# SwirlsV1_0.net
KiCad netlist of a schematic drawn in EAGLE
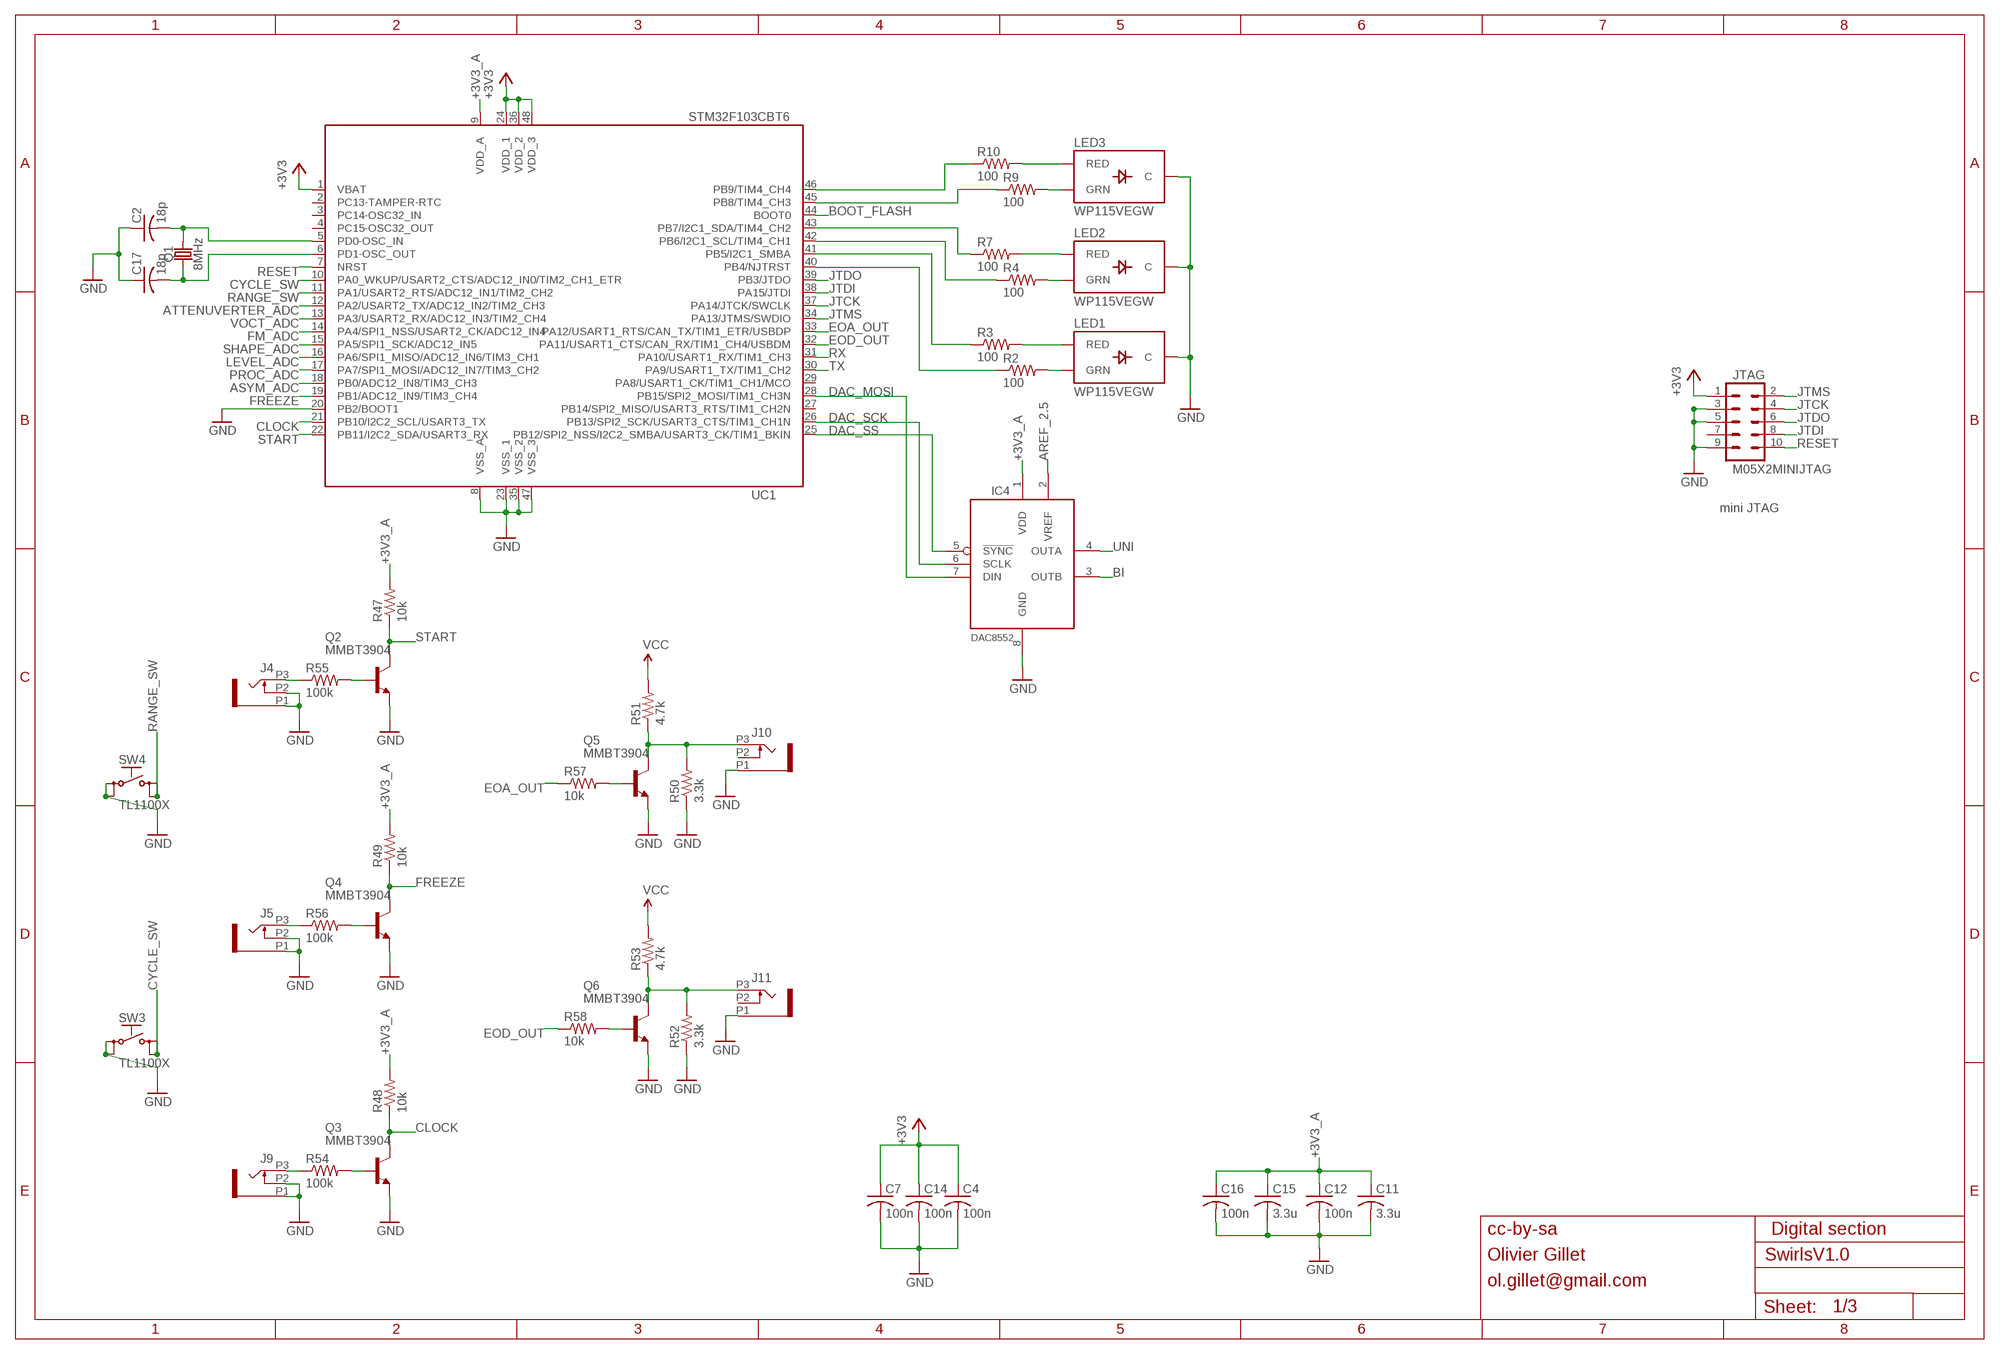
[diagram p0: schematic, sheet 1]
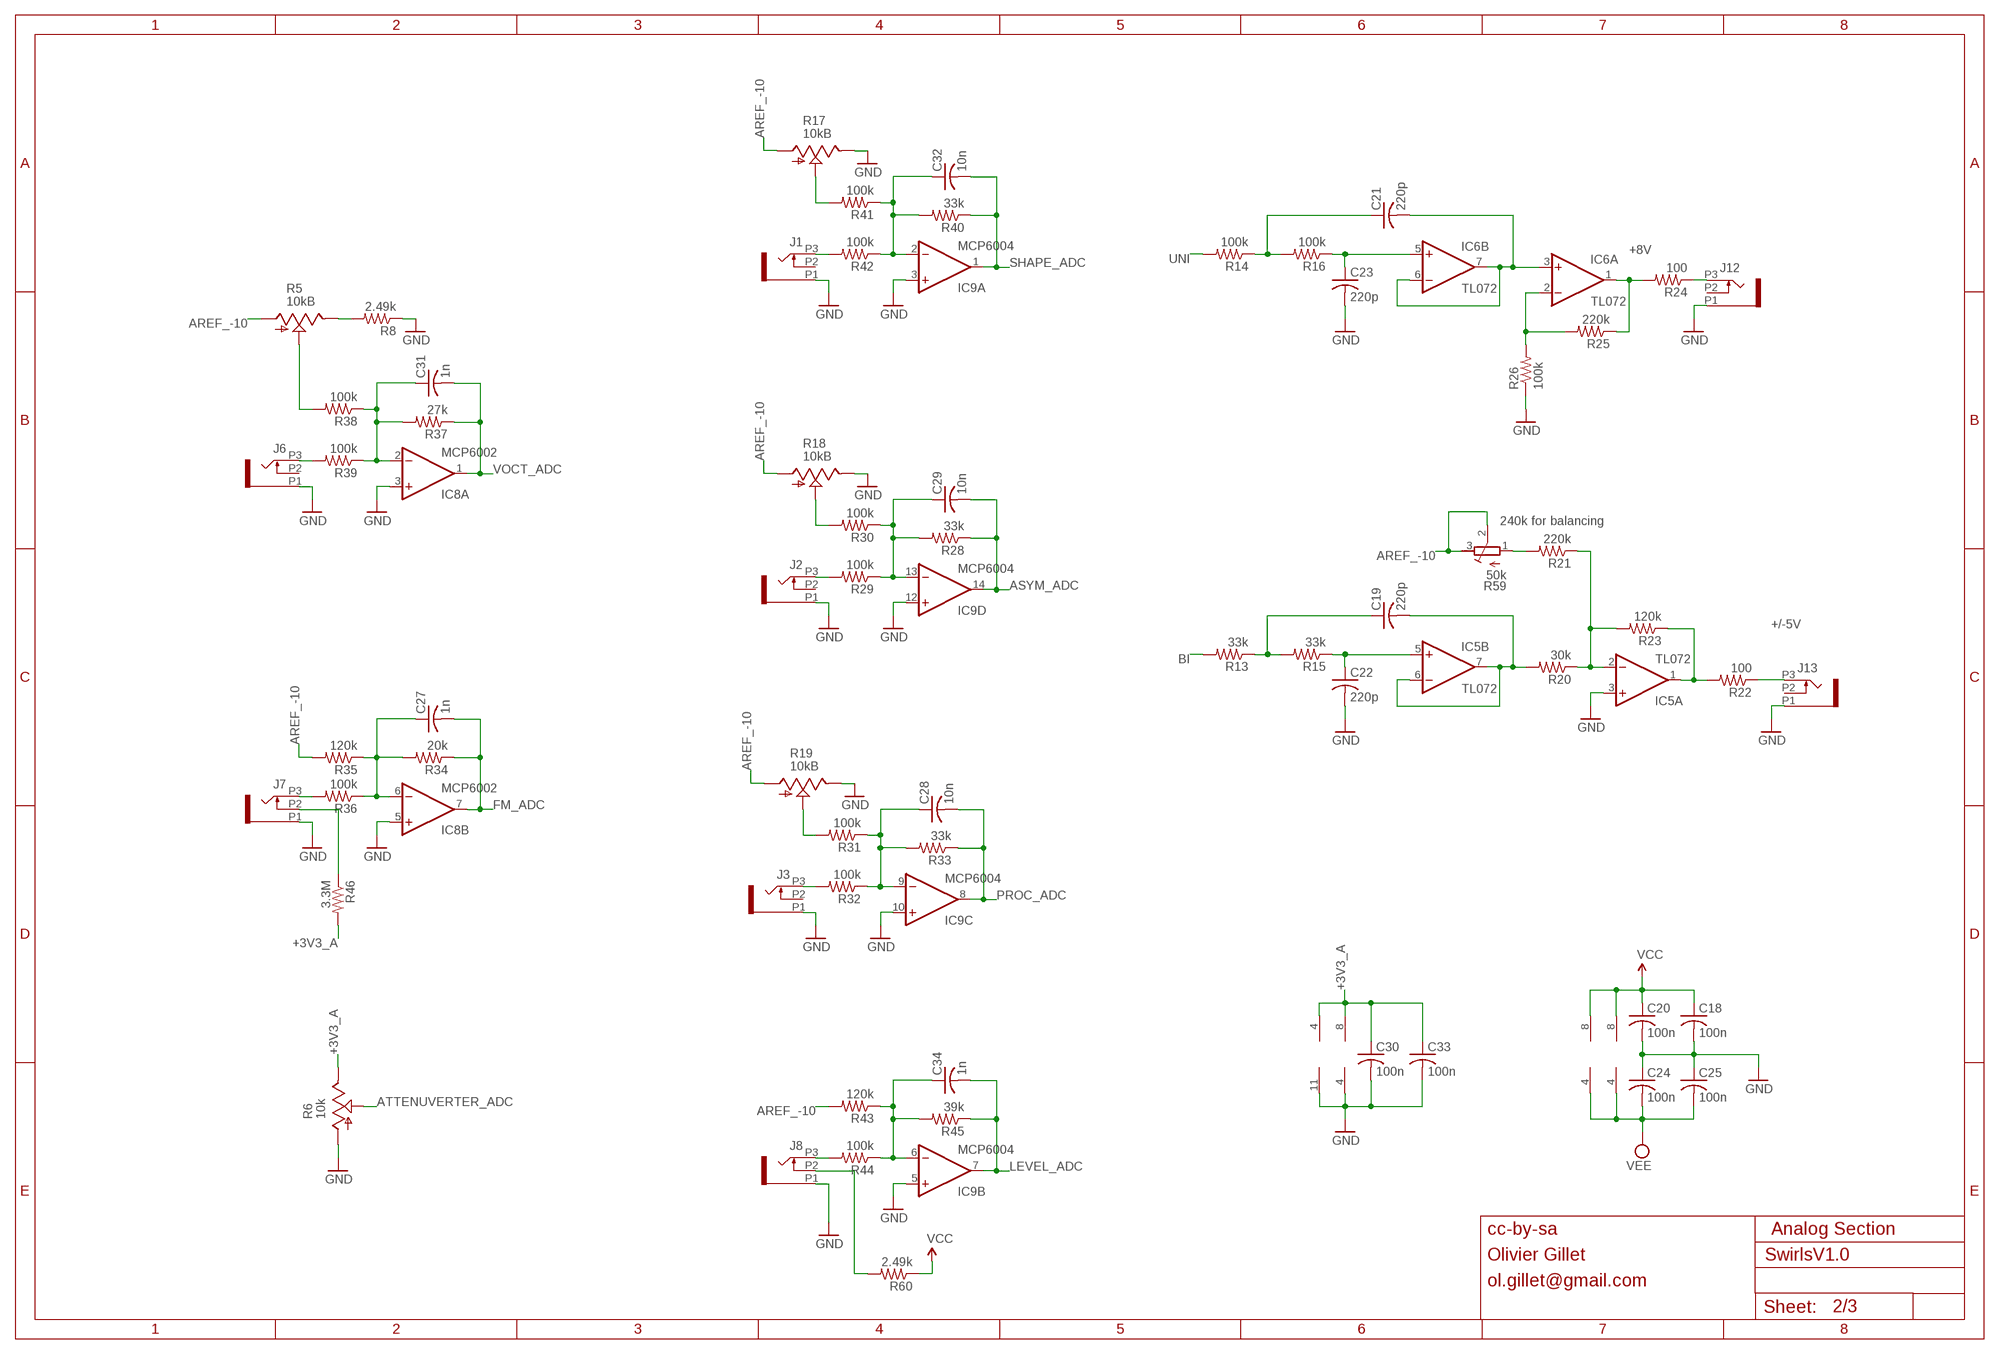
[diagram p1: schematic, sheet 2]
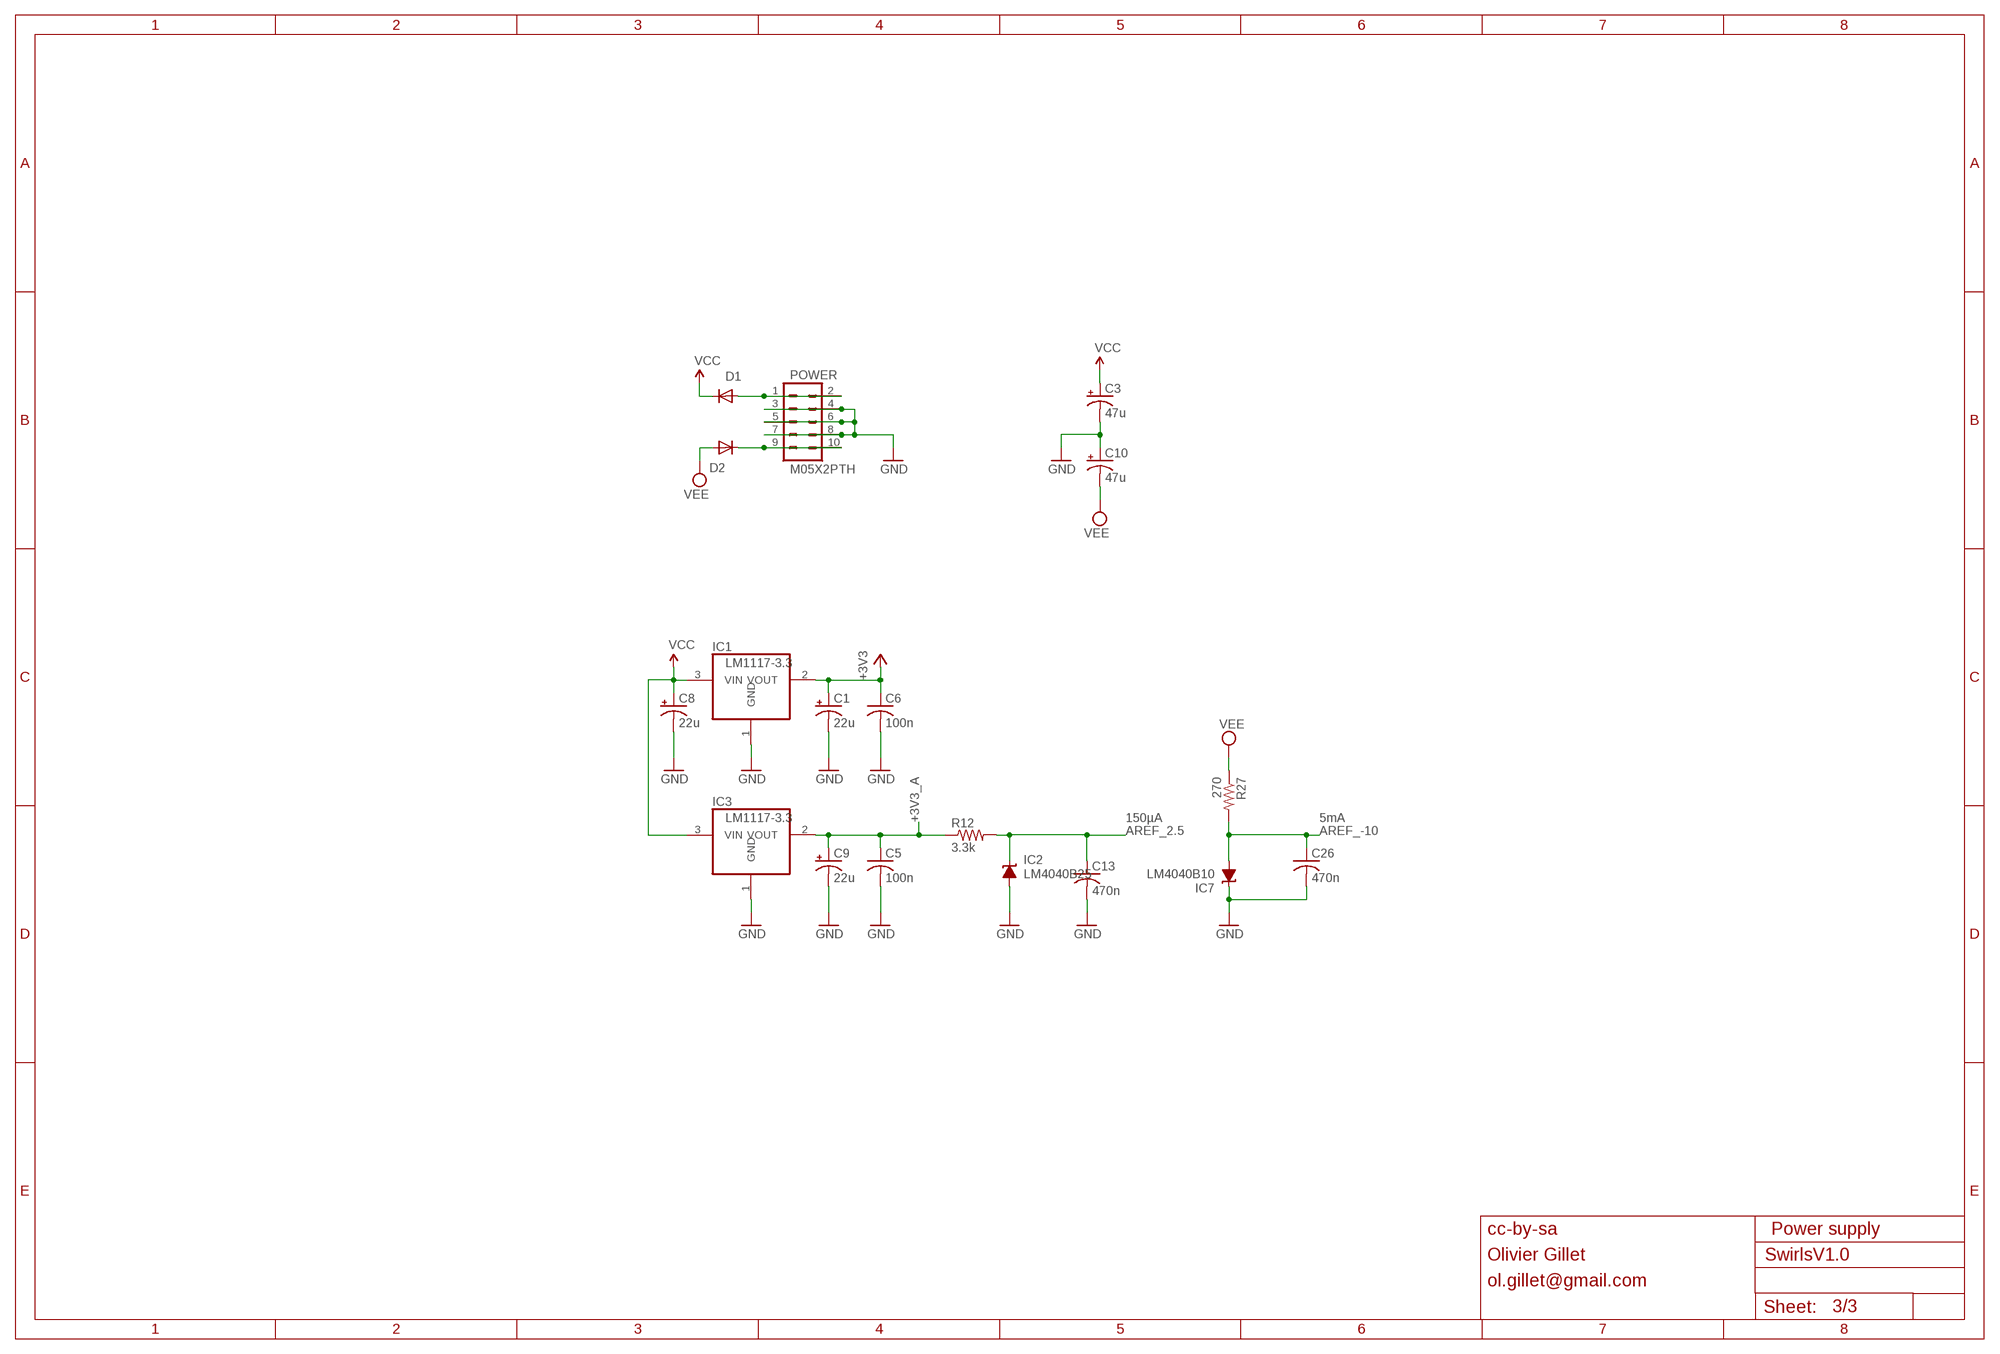
[diagram p2: schematic, sheet 3]

(export (version "E")
  (design (tool "Eeschema 10.0.6"))
  (components
    (comp (ref "C1")
      (value "22u")
      (footprint "eagle-import:PANASONIC_C")
      (libsource (lib "eagle-import") (part "CPOL-USC"))
    )
    (comp (ref "C3")
      (value "47u")
      (footprint "eagle-import:PANASONIC_D")
      (libsource (lib "eagle-import") (part "CPOL-USD"))
    )
    (comp (ref "C5")
      (value "100n")
      (footprint "eagle-import:C0603")
      (libsource (lib "eagle-import") (part "C-USC0603"))
    )
    (comp (ref "C6")
      (value "100n")
      (footprint "eagle-import:C0603")
      (libsource (lib "eagle-import") (part "C-USC0603"))
    )
    (comp (ref "C8")
      (value "22u")
      (footprint "eagle-import:PANASONIC_C")
      (libsource (lib "eagle-import") (part "CPOL-USC"))
    )
    (comp (ref "C9")
      (value "22u")
      (footprint "eagle-import:PANASONIC_C")
      (libsource (lib "eagle-import") (part "CPOL-USC"))
    )
    (comp (ref "C10")
      (value "47u")
      (footprint "eagle-import:PANASONIC_D")
      (libsource (lib "eagle-import") (part "CPOL-USD"))
    )
    (comp (ref "C13")
      (value "470n")
      (footprint "eagle-import:C0603")
      (libsource (lib "eagle-import") (part "C-USC0603"))
    )
    (comp (ref "C26")
      (value "470n")
      (footprint "eagle-import:C0603")
      (libsource (lib "eagle-import") (part "C-USC0603"))
    )
    (comp (ref "D1")
      (value "1N5819HW")
      (footprint "eagle-import:SOD123")
      (libsource (lib "eagle-import") (part "DIODE-SOD123"))
    )
    (comp (ref "D2")
      (value "1N5819HW")
      (footprint "eagle-import:SOD123")
      (libsource (lib "eagle-import") (part "DIODE-SOD123"))
    )
    (comp (ref "IC1")
      (value "LM1117-3.3")
      (footprint "eagle-import:SOT223")
      (libsource (lib "eagle-import") (part "REG1117"))
    )
    (comp (ref "IC2")
      (value "LM4040B25")
      (footprint "eagle-import:DBZ_R-PDSO-G3")
      (libsource (lib "eagle-import") (part "LM4041DBZB12"))
    )
    (comp (ref "IC3")
      (value "LM1117-3.3")
      (footprint "eagle-import:SOT223")
      (libsource (lib "eagle-import") (part "REG1117"))
    )
    (comp (ref "IC7")
      (value "LM4040B10")
      (footprint "eagle-import:DBZ_R-PDSO-G3")
      (libsource (lib "eagle-import") (part "LM4041DBZB12"))
    )
    (comp (ref "POWER")
      (value "M05X2PTH")
      (footprint "eagle-import:AVR_ICSP")
      (libsource (lib "eagle-import") (part "M05X2PTH"))
    )
    (comp (ref "R12")
      (value "3.3k")
      (footprint "eagle-import:R0603")
      (libsource (lib "eagle-import") (part "R-US_R0603"))
    )
    (comp (ref "R27")
      (value "270")
      (footprint "eagle-import:R0603")
      (libsource (lib "eagle-import") (part "R-US_R0603"))
    )
    (comp (ref "C18")
      (value "100n")
      (footprint "eagle-import:C0603")
      (libsource (lib "eagle-import") (part "C-USC0603"))
    )
    (comp (ref "C19")
      (value "220p")
      (footprint "eagle-import:C0603")
      (libsource (lib "eagle-import") (part "C-USC0603"))
    )
    (comp (ref "C20")
      (value "100n")
      (footprint "eagle-import:C0603")
      (libsource (lib "eagle-import") (part "C-USC0603"))
    )
    (comp (ref "C21")
      (value "220p")
      (footprint "eagle-import:C0603")
      (libsource (lib "eagle-import") (part "C-USC0603"))
    )
    (comp (ref "C22")
      (value "220p")
      (footprint "eagle-import:C0603")
      (libsource (lib "eagle-import") (part "C-USC0603"))
    )
    (comp (ref "C23")
      (value "220p")
      (footprint "eagle-import:C0603")
      (libsource (lib "eagle-import") (part "C-USC0603"))
    )
    (comp (ref "C24")
      (value "100n")
      (footprint "eagle-import:C0603")
      (libsource (lib "eagle-import") (part "C-USC0603"))
    )
    (comp (ref "C25")
      (value "100n")
      (footprint "eagle-import:C0603")
      (libsource (lib "eagle-import") (part "C-USC0603"))
    )
    (comp (ref "C27")
      (value "1n")
      (footprint "eagle-import:C0603")
      (libsource (lib "eagle-import") (part "C-USC0603"))
    )
    (comp (ref "C28")
      (value "10n")
      (footprint "eagle-import:C0603")
      (libsource (lib "eagle-import") (part "C-USC0603"))
    )
    (comp (ref "C29")
      (value "10n")
      (footprint "eagle-import:C0603")
      (libsource (lib "eagle-import") (part "C-USC0603"))
    )
    (comp (ref "C30")
      (value "100n")
      (footprint "eagle-import:C0603")
      (libsource (lib "eagle-import") (part "C-USC0603"))
    )
    (comp (ref "C31")
      (value "1n")
      (footprint "eagle-import:C0603")
      (libsource (lib "eagle-import") (part "C-USC0603"))
    )
    (comp (ref "C32")
      (value "10n")
      (footprint "eagle-import:C0603")
      (libsource (lib "eagle-import") (part "C-USC0603"))
    )
    (comp (ref "C33")
      (value "100n")
      (footprint "eagle-import:C0603")
      (libsource (lib "eagle-import") (part "C-USC0603"))
    )
    (comp (ref "C34")
      (value "1n")
      (footprint "eagle-import:C0603")
      (libsource (lib "eagle-import") (part "C-USC0603"))
    )
    (comp (ref "IC5")
      (value "TL072")
      (footprint "eagle-import:TSSOP-8")
      (libsource (lib "eagle-import") (part "TL072TSSOP"))
    )
    (comp (ref "IC6")
      (value "TL072")
      (footprint "eagle-import:TSSOP-8")
      (libsource (lib "eagle-import") (part "TL072TSSOP"))
    )
    (comp (ref "IC8")
      (value "MCP6002")
      (footprint "eagle-import:SO08")
      (libsource (lib "eagle-import") (part "TL072D"))
    )
    (comp (ref "IC9")
      (value "MCP6004")
      (footprint "eagle-import:TSSOP14")
      (libsource (lib "eagle-import") (part "MCP6004ST"))
    )
    (comp (ref "J1")
      (value "PJ301_GUI6")
      (footprint "eagle-import:OG-PJ301_VARIATIONS_WQP_PJ_301M6")
      (libsource (lib "eagle-import") (part "PJ301_GUI6"))
    )
    (comp (ref "J2")
      (value "PJ301_GUI6")
      (footprint "eagle-import:OG-PJ301_VARIATIONS_WQP_PJ_301M6")
      (libsource (lib "eagle-import") (part "PJ301_GUI6"))
    )
    (comp (ref "J3")
      (value "PJ301_GUI6")
      (footprint "eagle-import:OG-PJ301_VARIATIONS_WQP_PJ_301M6")
      (libsource (lib "eagle-import") (part "PJ301_GUI6"))
    )
    (comp (ref "J6")
      (value "PJ301_GUI6")
      (footprint "eagle-import:OG-PJ301_VARIATIONS_WQP_PJ_301M6")
      (libsource (lib "eagle-import") (part "PJ301_GUI6"))
    )
    (comp (ref "J7")
      (value "PJ301_GUI6")
      (footprint "eagle-import:OG-PJ301_VARIATIONS_WQP_PJ_301M6")
      (libsource (lib "eagle-import") (part "PJ301_GUI6"))
    )
    (comp (ref "J8")
      (value "PJ301_GUI6")
      (footprint "eagle-import:OG-PJ301_VARIATIONS_WQP_PJ_301M6")
      (libsource (lib "eagle-import") (part "PJ301_GUI6"))
    )
    (comp (ref "J12")
      (value "PJ301_GUI6")
      (footprint "eagle-import:OG-PJ301_VARIATIONS_WQP_PJ_301M6")
      (libsource (lib "eagle-import") (part "PJ301_GUI6"))
    )
    (comp (ref "J13")
      (value "PJ301_GUI6")
      (footprint "eagle-import:OG-PJ301_VARIATIONS_WQP_PJ_301M6")
      (libsource (lib "eagle-import") (part "PJ301_GUI6"))
    )
    (comp (ref "R5")
      (value "10kB")
      (footprint "eagle-import:ALPS_POT_VERTICAL_PS")
      (libsource (lib "eagle-import") (part "POT_USVERTICAL_PS"))
    )
    (comp (ref "R6")
      (value "10k")
      (footprint "eagle-import:ALPS_POT_VERTICAL_PS")
      (libsource (lib "eagle-import") (part "POT_USVERTICAL_PS"))
    )
    (comp (ref "R8")
      (value "2.49k")
      (footprint "eagle-import:R0603")
      (libsource (lib "eagle-import") (part "R-US_R0603"))
    )
    (comp (ref "R13")
      (value "33k")
      (footprint "eagle-import:R0603")
      (libsource (lib "eagle-import") (part "R-US_R0603"))
    )
    (comp (ref "R14")
      (value "100k")
      (footprint "eagle-import:R0603")
      (libsource (lib "eagle-import") (part "R-US_R0603"))
    )
    (comp (ref "R15")
      (value "33k")
      (footprint "eagle-import:R0603")
      (libsource (lib "eagle-import") (part "R-US_R0603"))
    )
    (comp (ref "R16")
      (value "100k")
      (footprint "eagle-import:R0603")
      (libsource (lib "eagle-import") (part "R-US_R0603"))
    )
    (comp (ref "R17")
      (value "10kB")
      (footprint "eagle-import:ALPS_POT_VERTICAL_PS")
      (libsource (lib "eagle-import") (part "POT_USVERTICAL_PS"))
    )
    (comp (ref "R18")
      (value "10kB")
      (footprint "eagle-import:ALPS_POT_VERTICAL_PS")
      (libsource (lib "eagle-import") (part "POT_USVERTICAL_PS"))
    )
    (comp (ref "R19")
      (value "10kB")
      (footprint "eagle-import:ALPS_POT_VERTICAL_PS")
      (libsource (lib "eagle-import") (part "POT_USVERTICAL_PS"))
    )
    (comp (ref "R20")
      (value "30k")
      (footprint "eagle-import:R0603")
      (libsource (lib "eagle-import") (part "R-US_R0603"))
    )
    (comp (ref "R21")
      (value "220k")
      (footprint "eagle-import:R0603")
      (libsource (lib "eagle-import") (part "R-US_R0603"))
    )
    (comp (ref "R22")
      (value "100")
      (footprint "eagle-import:R0603")
      (libsource (lib "eagle-import") (part "R-US_R0603"))
    )
    (comp (ref "R23")
      (value "120k")
      (footprint "eagle-import:R0603")
      (libsource (lib "eagle-import") (part "R-US_R0603"))
    )
    (comp (ref "R24")
      (value "100")
      (footprint "eagle-import:R0603")
      (libsource (lib "eagle-import") (part "R-US_R0603"))
    )
    (comp (ref "R25")
      (value "220k")
      (footprint "eagle-import:R0603")
      (libsource (lib "eagle-import") (part "R-US_R0603"))
    )
    (comp (ref "R26")
      (value "100k")
      (footprint "eagle-import:R0603")
      (libsource (lib "eagle-import") (part "R-US_R0603"))
    )
    (comp (ref "R28")
      (value "33k")
      (footprint "eagle-import:R0603")
      (libsource (lib "eagle-import") (part "R-US_R0603"))
    )
    (comp (ref "R29")
      (value "100k")
      (footprint "eagle-import:R0603")
      (libsource (lib "eagle-import") (part "R-US_R0603"))
    )
    (comp (ref "R30")
      (value "100k")
      (footprint "eagle-import:R0603")
      (libsource (lib "eagle-import") (part "R-US_R0603"))
    )
    (comp (ref "R31")
      (value "100k")
      (footprint "eagle-import:R0603")
      (libsource (lib "eagle-import") (part "R-US_R0603"))
    )
    (comp (ref "R32")
      (value "100k")
      (footprint "eagle-import:R0603")
      (libsource (lib "eagle-import") (part "R-US_R0603"))
    )
    (comp (ref "R33")
      (value "33k")
      (footprint "eagle-import:R0603")
      (libsource (lib "eagle-import") (part "R-US_R0603"))
    )
    (comp (ref "R34")
      (value "20k")
      (footprint "eagle-import:R0603")
      (libsource (lib "eagle-import") (part "R-US_R0603"))
    )
    (comp (ref "R35")
      (value "120k")
      (footprint "eagle-import:R0603")
      (libsource (lib "eagle-import") (part "R-US_R0603"))
    )
    (comp (ref "R36")
      (value "100k")
      (footprint "eagle-import:R0603")
      (libsource (lib "eagle-import") (part "R-US_R0603"))
    )
    (comp (ref "R37")
      (value "27k")
      (footprint "eagle-import:R0603")
      (libsource (lib "eagle-import") (part "R-US_R0603"))
    )
    (comp (ref "R38")
      (value "100k")
      (footprint "eagle-import:R0603")
      (libsource (lib "eagle-import") (part "R-US_R0603"))
    )
    (comp (ref "R39")
      (value "100k")
      (footprint "eagle-import:R0603")
      (libsource (lib "eagle-import") (part "R-US_R0603"))
    )
    (comp (ref "R40")
      (value "33k")
      (footprint "eagle-import:R0603")
      (libsource (lib "eagle-import") (part "R-US_R0603"))
    )
    (comp (ref "R41")
      (value "100k")
      (footprint "eagle-import:R0603")
      (libsource (lib "eagle-import") (part "R-US_R0603"))
    )
    (comp (ref "R42")
      (value "100k")
      (footprint "eagle-import:R0603")
      (libsource (lib "eagle-import") (part "R-US_R0603"))
    )
    (comp (ref "R43")
      (value "120k")
      (footprint "eagle-import:R0603")
      (libsource (lib "eagle-import") (part "R-US_R0603"))
    )
    (comp (ref "R44")
      (value "100k")
      (footprint "eagle-import:R0603")
      (libsource (lib "eagle-import") (part "R-US_R0603"))
    )
    (comp (ref "R45")
      (value "39k")
      (footprint "eagle-import:R0603")
      (libsource (lib "eagle-import") (part "R-US_R0603"))
    )
    (comp (ref "R46")
      (value "3.3M")
      (footprint "eagle-import:R0603")
      (libsource (lib "eagle-import") (part "R-US_R0603"))
    )
    (comp (ref "R59")
      (value "50k")
      (footprint "eagle-import:RTRIM3296W")
      (libsource (lib "eagle-import") (part "R-TRIMM3296W"))
    )
    (comp (ref "R60")
      (value "2.49k")
      (footprint "eagle-import:R0805")
      (libsource (lib "eagle-import") (part "R-US_R0805"))
    )
    (comp (ref "C2")
      (value "18p")
      (footprint "eagle-import:C0603")
      (libsource (lib "eagle-import") (part "C-USC0603"))
    )
    (comp (ref "C4")
      (value "100n")
      (footprint "eagle-import:C0603")
      (libsource (lib "eagle-import") (part "C-USC0603"))
    )
    (comp (ref "C7")
      (value "100n")
      (footprint "eagle-import:C0603")
      (libsource (lib "eagle-import") (part "C-USC0603"))
    )
    (comp (ref "C11")
      (value "3.3u")
      (footprint "eagle-import:C0603")
      (libsource (lib "eagle-import") (part "C-USC0603"))
    )
    (comp (ref "C12")
      (value "100n")
      (footprint "eagle-import:C0603")
      (libsource (lib "eagle-import") (part "C-USC0603"))
    )
    (comp (ref "C14")
      (value "100n")
      (footprint "eagle-import:C0603")
      (libsource (lib "eagle-import") (part "C-USC0603"))
    )
    (comp (ref "C15")
      (value "3.3u")
      (footprint "eagle-import:C0603")
      (libsource (lib "eagle-import") (part "C-USC0603"))
    )
    (comp (ref "C16")
      (value "100n")
      (footprint "eagle-import:C0603")
      (libsource (lib "eagle-import") (part "C-USC0603"))
    )
    (comp (ref "C17")
      (value "18p")
      (footprint "eagle-import:C0603")
      (libsource (lib "eagle-import") (part "C-USC0603"))
    )
    (comp (ref "IC4")
      (value "DAC8552")
      (footprint "eagle-import:MSOP-8")
      (libsource (lib "eagle-import") (part "DAC8552"))
    )
    (comp (ref "J4")
      (value "PJ301_GUI6")
      (footprint "eagle-import:OG-PJ301_VARIATIONS_WQP_PJ_301M6")
      (libsource (lib "eagle-import") (part "PJ301_GUI6"))
    )
    (comp (ref "J5")
      (value "PJ301_GUI6")
      (footprint "eagle-import:OG-PJ301_VARIATIONS_WQP_PJ_301M6")
      (libsource (lib "eagle-import") (part "PJ301_GUI6"))
    )
    (comp (ref "J9")
      (value "PJ301_GUI6")
      (footprint "eagle-import:OG-PJ301_VARIATIONS_WQP_PJ_301M6")
      (libsource (lib "eagle-import") (part "PJ301_GUI6"))
    )
    (comp (ref "J10")
      (value "PJ301_GUI6")
      (footprint "eagle-import:OG-PJ301_VARIATIONS_WQP_PJ_301M6")
      (libsource (lib "eagle-import") (part "PJ301_GUI6"))
    )
    (comp (ref "J11")
      (value "PJ301_GUI6")
      (footprint "eagle-import:OG-PJ301_VARIATIONS_WQP_PJ_301M6")
      (libsource (lib "eagle-import") (part "PJ301_GUI6"))
    )
    (comp (ref "JTAG")
      (value "M05X2MINIJTAG")
      (footprint "eagle-import:2X5-1.27")
      (libsource (lib "eagle-import") (part "M05X2MINIJTAG"))
    )
    (comp (ref "LED1")
      (value "WP115VEGW")
      (footprint "eagle-import:LED-BICOLOR-THROUGHHOLE")
      (libsource (lib "eagle-import") (part "LED-BICOLOR-THROUGHHOLE"))
    )
    (comp (ref "LED2")
      (value "WP115VEGW")
      (footprint "eagle-import:LED-BICOLOR-THROUGHHOLE")
      (libsource (lib "eagle-import") (part "LED-BICOLOR-THROUGHHOLE"))
    )
    (comp (ref "LED3")
      (value "WP115VEGW")
      (footprint "eagle-import:LED-BICOLOR-THROUGHHOLE")
      (libsource (lib "eagle-import") (part "LED-BICOLOR-THROUGHHOLE"))
    )
    (comp (ref "Q1")
      (value "8MHz")
      (footprint "eagle-import:HC49UP")
      (libsource (lib "eagle-import") (part "CRYSTAL-8MHZSMD-HC49UP"))
    )
    (comp (ref "Q2")
      (value "MMBT3904")
      (footprint "eagle-import:SOT23-BEC")
      (libsource (lib "eagle-import") (part "-NPN-SOT23-BECMMBT3904LT1"))
    )
    (comp (ref "Q3")
      (value "MMBT3904")
      (footprint "eagle-import:SOT23-BEC")
      (libsource (lib "eagle-import") (part "-NPN-SOT23-BECMMBT3904LT1"))
    )
    (comp (ref "Q4")
      (value "MMBT3904")
      (footprint "eagle-import:SOT23-BEC")
      (libsource (lib "eagle-import") (part "-NPN-SOT23-BECMMBT3904LT1"))
    )
    (comp (ref "Q5")
      (value "MMBT3904")
      (footprint "eagle-import:SOT23-BEC")
      (libsource (lib "eagle-import") (part "-NPN-SOT23-BECMMBT3904LT1"))
    )
    (comp (ref "Q6")
      (value "MMBT3904")
      (footprint "eagle-import:SOT23-BEC")
      (libsource (lib "eagle-import") (part "-NPN-SOT23-BECMMBT3904LT1"))
    )
    (comp (ref "R2")
      (value "100")
      (footprint "eagle-import:R0603")
      (libsource (lib "eagle-import") (part "R-US_R0603"))
    )
    (comp (ref "R3")
      (value "100")
      (footprint "eagle-import:R0603")
      (libsource (lib "eagle-import") (part "R-US_R0603"))
    )
    (comp (ref "R4")
      (value "100")
      (footprint "eagle-import:R0603")
      (libsource (lib "eagle-import") (part "R-US_R0603"))
    )
    (comp (ref "R7")
      (value "100")
      (footprint "eagle-import:R0603")
      (libsource (lib "eagle-import") (part "R-US_R0603"))
    )
    (comp (ref "R9")
      (value "100")
      (footprint "eagle-import:R0603")
      (libsource (lib "eagle-import") (part "R-US_R0603"))
    )
    (comp (ref "R10")
      (value "100")
      (footprint "eagle-import:R0603")
      (libsource (lib "eagle-import") (part "R-US_R0603"))
    )
    (comp (ref "R47")
      (value "10k")
      (footprint "eagle-import:R0603")
      (libsource (lib "eagle-import") (part "R-US_R0603"))
    )
    (comp (ref "R48")
      (value "10k")
      (footprint "eagle-import:R0603")
      (libsource (lib "eagle-import") (part "R-US_R0603"))
    )
    (comp (ref "R49")
      (value "10k")
      (footprint "eagle-import:R0603")
      (libsource (lib "eagle-import") (part "R-US_R0603"))
    )
    (comp (ref "R50")
      (value "3.3k")
      (footprint "eagle-import:R0603")
      (libsource (lib "eagle-import") (part "R-US_R0603"))
    )
    (comp (ref "R51")
      (value "4.7k")
      (footprint "eagle-import:R0603")
      (libsource (lib "eagle-import") (part "R-US_R0603"))
    )
    (comp (ref "R52")
      (value "3.3k")
      (footprint "eagle-import:R0603")
      (libsource (lib "eagle-import") (part "R-US_R0603"))
    )
    (comp (ref "R53")
      (value "4.7k")
      (footprint "eagle-import:R0603")
      (libsource (lib "eagle-import") (part "R-US_R0603"))
    )
    (comp (ref "R54")
      (value "100k")
      (footprint "eagle-import:R0603")
      (libsource (lib "eagle-import") (part "R-US_R0603"))
    )
    (comp (ref "R55")
      (value "100k")
      (footprint "eagle-import:R0603")
      (libsource (lib "eagle-import") (part "R-US_R0603"))
    )
    (comp (ref "R56")
      (value "100k")
      (footprint "eagle-import:R0603")
      (libsource (lib "eagle-import") (part "R-US_R0603"))
    )
    (comp (ref "R57")
      (value "10k")
      (footprint "eagle-import:R0603")
      (libsource (lib "eagle-import") (part "R-US_R0603"))
    )
    (comp (ref "R58")
      (value "10k")
      (footprint "eagle-import:R0603")
      (libsource (lib "eagle-import") (part "R-US_R0603"))
    )
    (comp (ref "SW3")
      (value "TL1100X")
      (footprint "eagle-import:TL1100X")
      (libsource (lib "eagle-import") (part "TL1100X"))
    )
    (comp (ref "SW4")
      (value "TL1100X")
      (footprint "eagle-import:TL1100X")
      (libsource (lib "eagle-import") (part "TL1100X"))
    )
    (comp (ref "UC1")
      (value "STM32F103CBT6")
      (footprint "eagle-import:LQFP48")
      (libsource (lib "eagle-import") (part "STM32F103CB"))
    )
  )
  (nets
    (net (code "1") (name "+3V3") (class "Default")
      (node (ref "C1") (pin "+") (pinfunction "+_+") (pintype "passive"))
      (node (ref "C14") (pin "1") (pinfunction "1_1") (pintype "passive"))
      (node (ref "C4") (pin "1") (pinfunction "1_1") (pintype "passive"))
      (node (ref "C6") (pin "1") (pinfunction "1_1") (pintype "passive"))
      (node (ref "C7") (pin "1") (pinfunction "1_1") (pintype "passive"))
      (node (ref "IC1") (pin "2") (pinfunction "VOUT_2") (pintype "output"))
      (node (ref "JTAG") (pin "1") (pinfunction "1_1") (pintype "passive"))
      (node (ref "UC1") (pin "1") (pinfunction "VBAT_1") (pintype "power_in"))
      (node (ref "UC1") (pin "24") (pinfunction "VDD_1_24") (pintype "power_in"))
      (node (ref "UC1") (pin "36") (pinfunction "VDD_2_36") (pintype "power_in"))
      (node (ref "UC1") (pin "48") (pinfunction "VDD_3_48") (pintype "power_in"))
    )
    (net (code "2") (name "+3V3_A") (class "Default")
      (node (ref "C11") (pin "1") (pinfunction "1_1") (pintype "passive"))
      (node (ref "C12") (pin "1") (pinfunction "1_1") (pintype "passive"))
      (node (ref "C15") (pin "1") (pinfunction "1_1") (pintype "passive"))
      (node (ref "C16") (pin "1") (pinfunction "1_1") (pintype "passive"))
      (node (ref "C30") (pin "1") (pinfunction "1_1") (pintype "passive"))
      (node (ref "C33") (pin "1") (pinfunction "1_1") (pintype "passive"))
      (node (ref "C5") (pin "1") (pinfunction "1_1") (pintype "passive"))
      (node (ref "C9") (pin "+") (pinfunction "+_+") (pintype "passive"))
      (node (ref "IC3") (pin "2") (pinfunction "VOUT_2") (pintype "output"))
      (node (ref "IC4") (pin "1") (pinfunction "VDD_1") (pintype "power_in"))
      (node (ref "IC8") (pin "8") (pinfunction "V+_8") (pintype "power_in"))
      (node (ref "IC9") (pin "4") (pinfunction "V+_4") (pintype "power_in"))
      (node (ref "R12") (pin "1") (pinfunction "1_1") (pintype "passive"))
      (node (ref "R46") (pin "2") (pinfunction "2_2") (pintype "passive"))
      (node (ref "R47") (pin "2") (pinfunction "2_2") (pintype "passive"))
      (node (ref "R48") (pin "2") (pinfunction "2_2") (pintype "passive"))
      (node (ref "R49") (pin "2") (pinfunction "2_2") (pintype "passive"))
      (node (ref "R6") (pin "P$1") (pinfunction "E_P$1") (pintype "passive"))
      (node (ref "UC1") (pin "9") (pinfunction "VDD_A_9") (pintype "power_in"))
    )
    (net (code "3") (name "AREF_-10") (class "Default")
      (node (ref "C26") (pin "1") (pinfunction "1_1") (pintype "passive"))
      (node (ref "IC7") (pin "2") (pinfunction "A_2") (pintype "passive"))
      (node (ref "R17") (pin "P$3") (pinfunction "A_P$3") (pintype "passive"))
      (node (ref "R18") (pin "P$3") (pinfunction "A_P$3") (pintype "passive"))
      (node (ref "R19") (pin "P$3") (pinfunction "A_P$3") (pintype "passive"))
      (node (ref "R27") (pin "2") (pinfunction "2_2") (pintype "passive"))
      (node (ref "R35") (pin "2") (pinfunction "2_2") (pintype "passive"))
      (node (ref "R43") (pin "2") (pinfunction "2_2") (pintype "passive"))
      (node (ref "R5") (pin "P$3") (pinfunction "A_P$3") (pintype "passive"))
      (node (ref "R59") (pin "2") (pinfunction "S_2") (pintype "passive"))
      (node (ref "R59") (pin "3") (pinfunction "E_3") (pintype "passive"))
    )
    (net (code "4") (name "AREF_2.5") (class "Default")
      (node (ref "C13") (pin "1") (pinfunction "1_1") (pintype "passive"))
      (node (ref "IC2") (pin "1") (pinfunction "C_1") (pintype "passive"))
      (node (ref "IC4") (pin "2") (pinfunction "VREF_2") (pintype "power_in"))
      (node (ref "R12") (pin "2") (pinfunction "2_2") (pintype "passive"))
    )
    (net (code "5") (name "ASYM_ADC") (class "Default")
      (node (ref "C29") (pin "2") (pinfunction "2_2") (pintype "passive"))
      (node (ref "IC9") (pin "14") (pinfunction "OUT_14") (pintype "output"))
      (node (ref "R28") (pin "1") (pinfunction "1_1") (pintype "passive"))
      (node (ref "UC1") (pin "18") (pinfunction "PB0/ADC12_IN8/TIM3_CH3_18") (pintype "bidirectional"))
    )
    (net (code "6") (name "ATTENUVERTER_ADC") (class "Default")
      (node (ref "R6") (pin "P$2") (pinfunction "S_P$2") (pintype "passive"))
      (node (ref "UC1") (pin "12") (pinfunction "PA2/USART2_TX/ADC12_IN2/TIM2_CH3_12") (pintype "bidirectional"))
    )
    (net (code "7") (name "BI") (class "Default")
      (node (ref "IC4") (pin "3") (pinfunction "OUTB_3") (pintype "input"))
      (node (ref "R13") (pin "2") (pinfunction "2_2") (pintype "passive"))
    )
    (net (code "8") (name "BOOT_FLASH") (class "Default")
      (node (ref "UC1") (pin "44") (pinfunction "BOOT0_44") (pintype "input"))
    )
    (net (code "9") (name "CLOCK") (class "Default")
      (node (ref "Q3") (pin "C") (pinfunction "C_C") (pintype "passive"))
      (node (ref "R48") (pin "1") (pinfunction "1_1") (pintype "passive"))
      (node (ref "UC1") (pin "21") (pinfunction "PB10/I2C2_SCL/USART3_TX_21") (pintype "input"))
    )
    (net (code "10") (name "CYCLE_SW") (class "Default")
      (node (ref "SW3") (pin "3") (pinfunction "S_3") (pintype "passive"))
      (node (ref "SW3") (pin "4") (pinfunction "S1_4") (pintype "passive"))
      (node (ref "UC1") (pin "10") (pinfunction "PA0_WKUP/USART2_CTS/ADC12_IN0/TIM2_CH1_ETR_10") (pintype "bidirectional"))
    )
    (net (code "11") (name "DAC_MOSI") (class "Default")
      (node (ref "IC4") (pin "7") (pinfunction "DIN_7") (pintype "bidirectional"))
      (node (ref "UC1") (pin "28") (pinfunction "PB15/SPI2_MOSI/TIM1_CH3N_28") (pintype "input"))
    )
    (net (code "12") (name "DAC_SCK") (class "Default")
      (node (ref "IC4") (pin "6") (pinfunction "SCLK_6") (pintype "bidirectional"))
      (node (ref "UC1") (pin "26") (pinfunction "PB13/SPI2_SCK/USART3_CTS/TIM1_CH1N_26") (pintype "input"))
    )
    (net (code "13") (name "DAC_SS") (class "Default")
      (node (ref "IC4") (pin "5") (pinfunction "~{SYNC}_5") (pintype "bidirectional"))
      (node (ref "UC1") (pin "25") (pinfunction "PB12/SPI2_NSS/I2C2_SMBA/USART3_CK/TIM1_BKIN_25") (pintype "input"))
    )
    (net (code "14") (name "EOA_OUT") (class "Default")
      (node (ref "R57") (pin "1") (pinfunction "1_1") (pintype "passive"))
      (node (ref "UC1") (pin "33") (pinfunction "PA12/USART1_RTS/CAN_TX/TIM1_ETR/USBDP_33") (pintype "bidirectional"))
    )
    (net (code "15") (name "EOD_OUT") (class "Default")
      (node (ref "R58") (pin "1") (pinfunction "1_1") (pintype "passive"))
      (node (ref "UC1") (pin "32") (pinfunction "PA11/USART1_CTS/CAN_RX/TIM1_CH4/USBDM_32") (pintype "bidirectional"))
    )
    (net (code "16") (name "FM_ADC") (class "Default")
      (node (ref "C27") (pin "2") (pinfunction "2_2") (pintype "passive"))
      (node (ref "IC8") (pin "7") (pinfunction "OUT_7") (pintype "output"))
      (node (ref "R34") (pin "1") (pinfunction "1_1") (pintype "passive"))
      (node (ref "UC1") (pin "14") (pinfunction "PA4/SPI1_NSS/USART2_CK/ADC12_IN4_14") (pintype "bidirectional"))
    )
    (net (code "17") (name "FREEZE") (class "Default")
      (node (ref "Q4") (pin "C") (pinfunction "C_C") (pintype "passive"))
      (node (ref "R49") (pin "1") (pinfunction "1_1") (pintype "passive"))
      (node (ref "UC1") (pin "19") (pinfunction "PB1/ADC12_IN9/TIM3_CH4_19") (pintype "bidirectional"))
    )
    (net (code "18") (name "GND") (class "Default")
      (node (ref "C1") (pin "-") (pinfunction "-_-") (pintype "passive"))
      (node (ref "C10") (pin "+") (pinfunction "+_+") (pintype "passive"))
      (node (ref "C11") (pin "2") (pinfunction "2_2") (pintype "passive"))
      (node (ref "C12") (pin "2") (pinfunction "2_2") (pintype "passive"))
      (node (ref "C13") (pin "2") (pinfunction "2_2") (pintype "passive"))
      (node (ref "C14") (pin "2") (pinfunction "2_2") (pintype "passive"))
      (node (ref "C15") (pin "2") (pinfunction "2_2") (pintype "passive"))
      (node (ref "C16") (pin "2") (pinfunction "2_2") (pintype "passive"))
      (node (ref "C17") (pin "1") (pinfunction "1_1") (pintype "passive"))
      (node (ref "C18") (pin "2") (pinfunction "2_2") (pintype "passive"))
      (node (ref "C2") (pin "1") (pinfunction "1_1") (pintype "passive"))
      (node (ref "C20") (pin "2") (pinfunction "2_2") (pintype "passive"))
      (node (ref "C22") (pin "2") (pinfunction "2_2") (pintype "passive"))
      (node (ref "C23") (pin "2") (pinfunction "2_2") (pintype "passive"))
      (node (ref "C24") (pin "1") (pinfunction "1_1") (pintype "passive"))
      (node (ref "C25") (pin "1") (pinfunction "1_1") (pintype "passive"))
      (node (ref "C26") (pin "2") (pinfunction "2_2") (pintype "passive"))
      (node (ref "C3") (pin "-") (pinfunction "-_-") (pintype "passive"))
      (node (ref "C30") (pin "2") (pinfunction "2_2") (pintype "passive"))
      (node (ref "C33") (pin "2") (pinfunction "2_2") (pintype "passive"))
      (node (ref "C4") (pin "2") (pinfunction "2_2") (pintype "passive"))
      (node (ref "C5") (pin "2") (pinfunction "2_2") (pintype "passive"))
      (node (ref "C6") (pin "2") (pinfunction "2_2") (pintype "passive"))
      (node (ref "C7") (pin "2") (pinfunction "2_2") (pintype "passive"))
      (node (ref "C8") (pin "-") (pinfunction "-_-") (pintype "passive"))
      (node (ref "C9") (pin "-") (pinfunction "-_-") (pintype "passive"))
      (node (ref "IC1") (pin "1") (pinfunction "GND_1") (pintype "power_in"))
      (node (ref "IC2") (pin "2") (pinfunction "A_2") (pintype "passive"))
      (node (ref "IC3") (pin "1") (pinfunction "GND_1") (pintype "power_in"))
      (node (ref "IC4") (pin "8") (pinfunction "GND_8") (pintype "power_in"))
      (node (ref "IC5") (pin "3") (pinfunction "+IN_3") (pintype "input"))
      (node (ref "IC7") (pin "1") (pinfunction "C_1") (pintype "passive"))
      (node (ref "IC8") (pin "3") (pinfunction "+IN_3") (pintype "input"))
      (node (ref "IC8") (pin "4") (pinfunction "V-_4") (pintype "power_in"))
      (node (ref "IC8") (pin "5") (pinfunction "+IN_5") (pintype "input"))
      (node (ref "IC9") (pin "10") (pinfunction "+IN_10") (pintype "input"))
      (node (ref "IC9") (pin "11") (pinfunction "V-_11") (pintype "power_in"))
      (node (ref "IC9") (pin "12") (pinfunction "+IN_12") (pintype "input"))
      (node (ref "IC9") (pin "3") (pinfunction "+IN_3") (pintype "input"))
      (node (ref "IC9") (pin "5") (pinfunction "+IN_5") (pintype "input"))
      (node (ref "J1") (pin "P1") (pinfunction "1_P1") (pintype "passive"))
      (node (ref "J10") (pin "P1") (pinfunction "1_P1") (pintype "passive"))
      (node (ref "J11") (pin "P1") (pinfunction "1_P1") (pintype "passive"))
      (node (ref "J12") (pin "P1") (pinfunction "1_P1") (pintype "passive"))
      (node (ref "J13") (pin "P1") (pinfunction "1_P1") (pintype "passive"))
      (node (ref "J2") (pin "P1") (pinfunction "1_P1") (pintype "passive"))
      (node (ref "J3") (pin "P1") (pinfunction "1_P1") (pintype "passive"))
      (node (ref "J4") (pin "P1") (pinfunction "1_P1") (pintype "passive"))
      (node (ref "J4") (pin "P2") (pinfunction "2_P2") (pintype "passive"))
      (node (ref "J5") (pin "P1") (pinfunction "1_P1") (pintype "passive"))
      (node (ref "J5") (pin "P2") (pinfunction "2_P2") (pintype "passive"))
      (node (ref "J6") (pin "P1") (pinfunction "1_P1") (pintype "passive"))
      (node (ref "J7") (pin "P1") (pinfunction "1_P1") (pintype "passive"))
      (node (ref "J8") (pin "P1") (pinfunction "1_P1") (pintype "passive"))
      (node (ref "J9") (pin "P1") (pinfunction "1_P1") (pintype "passive"))
      (node (ref "J9") (pin "P2") (pinfunction "2_P2") (pintype "passive"))
      (node (ref "JTAG") (pin "3") (pinfunction "3_3") (pintype "passive"))
      (node (ref "JTAG") (pin "5") (pinfunction "5_5") (pintype "passive"))
      (node (ref "JTAG") (pin "9") (pinfunction "9_9") (pintype "passive"))
      (node (ref "LED1") (pin "2") (pinfunction "C_2") (pintype "bidirectional"))
      (node (ref "LED2") (pin "2") (pinfunction "C_2") (pintype "bidirectional"))
      (node (ref "LED3") (pin "2") (pinfunction "C_2") (pintype "bidirectional"))
      (node (ref "POWER") (pin "3") (pinfunction "3_3") (pintype "passive"))
      (node (ref "POWER") (pin "4") (pinfunction "4_4") (pintype "passive"))
      (node (ref "POWER") (pin "5") (pinfunction "5_5") (pintype "passive"))
      (node (ref "POWER") (pin "6") (pinfunction "6_6") (pintype "passive"))
      (node (ref "POWER") (pin "7") (pinfunction "7_7") (pintype "passive"))
      (node (ref "POWER") (pin "8") (pinfunction "8_8") (pintype "passive"))
      (node (ref "Q2") (pin "E") (pinfunction "E_E") (pintype "passive"))
      (node (ref "Q3") (pin "E") (pinfunction "E_E") (pintype "passive"))
      (node (ref "Q4") (pin "E") (pinfunction "E_E") (pintype "passive"))
      (node (ref "Q5") (pin "E") (pinfunction "E_E") (pintype "passive"))
      (node (ref "Q6") (pin "E") (pinfunction "E_E") (pintype "passive"))
      (node (ref "R17") (pin "P$1") (pinfunction "E_P$1") (pintype "passive"))
      (node (ref "R18") (pin "P$1") (pinfunction "E_P$1") (pintype "passive"))
      (node (ref "R19") (pin "P$1") (pinfunction "E_P$1") (pintype "passive"))
      (node (ref "R26") (pin "1") (pinfunction "1_1") (pintype "passive"))
      (node (ref "R50") (pin "1") (pinfunction "1_1") (pintype "passive"))
      (node (ref "R52") (pin "1") (pinfunction "1_1") (pintype "passive"))
      (node (ref "R6") (pin "P$3") (pinfunction "A_P$3") (pintype "passive"))
      (node (ref "R8") (pin "1") (pinfunction "1_1") (pintype "passive"))
      (node (ref "SW3") (pin "1") (pinfunction "P_1") (pintype "passive"))
      (node (ref "SW3") (pin "2") (pinfunction "P1_2") (pintype "passive"))
      (node (ref "SW4") (pin "1") (pinfunction "P_1") (pintype "passive"))
      (node (ref "SW4") (pin "2") (pinfunction "P1_2") (pintype "passive"))
      (node (ref "UC1") (pin "20") (pinfunction "PB2/BOOT1_20") (pintype "bidirectional"))
      (node (ref "UC1") (pin "23") (pinfunction "VSS_1_23") (pintype "power_in"))
      (node (ref "UC1") (pin "35") (pinfunction "VSS_2_35") (pintype "power_in"))
      (node (ref "UC1") (pin "47") (pinfunction "VSS_3_47") (pintype "power_in"))
      (node (ref "UC1") (pin "8") (pinfunction "VSS_A_8") (pintype "power_in"))
    )
    (net (code "19") (name "JTCK") (class "Default")
      (node (ref "JTAG") (pin "4") (pinfunction "4_4") (pintype "passive"))
      (node (ref "UC1") (pin "37") (pinfunction "PA14/JTCK/SWCLK_37") (pintype "bidirectional"))
    )
    (net (code "20") (name "JTDI") (class "Default")
      (node (ref "JTAG") (pin "8") (pinfunction "8_8") (pintype "passive"))
      (node (ref "UC1") (pin "38") (pinfunction "PA15/JTDI_38") (pintype "bidirectional"))
    )
    (net (code "21") (name "JTDO") (class "Default")
      (node (ref "JTAG") (pin "6") (pinfunction "6_6") (pintype "passive"))
      (node (ref "UC1") (pin "39") (pinfunction "PB3/JTDO_39") (pintype "bidirectional"))
    )
    (net (code "22") (name "JTMS") (class "Default")
      (node (ref "JTAG") (pin "2") (pinfunction "2_2") (pintype "passive"))
      (node (ref "UC1") (pin "34") (pinfunction "PA13/JTMS/SWDIO_34") (pintype "bidirectional"))
    )
    (net (code "23") (name "LEVEL_ADC") (class "Default")
      (node (ref "C34") (pin "2") (pinfunction "2_2") (pintype "passive"))
      (node (ref "IC9") (pin "7") (pinfunction "OUT_7") (pintype "output"))
      (node (ref "R45") (pin "1") (pinfunction "1_1") (pintype "passive"))
      (node (ref "UC1") (pin "16") (pinfunction "PA6/SPI1_MISO/ADC12_IN6/TIM3_CH1_16") (pintype "bidirectional"))
    )
    (net (code "24") (name "Net-(C19-Pad1)") (class "Default")
      (node (ref "C19") (pin "1") (pinfunction "1_1") (pintype "passive"))
      (node (ref "R13") (pin "1") (pinfunction "1_1") (pintype "passive"))
      (node (ref "R15") (pin "2") (pinfunction "2_2") (pintype "passive"))
    )
    (net (code "25") (name "Net-(C21-Pad1)") (class "Default")
      (node (ref "C21") (pin "1") (pinfunction "1_1") (pintype "passive"))
      (node (ref "R14") (pin "1") (pinfunction "1_1") (pintype "passive"))
      (node (ref "R16") (pin "2") (pinfunction "2_2") (pintype "passive"))
    )
    (net (code "26") (name "Net-(D1-PadA)") (class "Default")
      (node (ref "D1") (pin "A") (pinfunction "A_A") (pintype "passive"))
      (node (ref "POWER") (pin "1") (pinfunction "1_1") (pintype "passive"))
      (node (ref "POWER") (pin "2") (pinfunction "2_2") (pintype "passive"))
    )
    (net (code "27") (name "Net-(D2-PadC)") (class "Default")
      (node (ref "D2") (pin "C") (pinfunction "C_C") (pintype "passive"))
      (node (ref "POWER") (pin "10") (pinfunction "10_10") (pintype "passive"))
      (node (ref "POWER") (pin "9") (pinfunction "9_9") (pintype "passive"))
    )
    (net (code "28") (name "Net-(IC5A--IN)") (class "Default")
      (node (ref "IC5") (pin "2") (pinfunction "-IN_2") (pintype "input"))
      (node (ref "R20") (pin "1") (pinfunction "1_1") (pintype "passive"))
      (node (ref "R21") (pin "1") (pinfunction "1_1") (pintype "passive"))
      (node (ref "R23") (pin "2") (pinfunction "2_2") (pintype "passive"))
    )
    (net (code "29") (name "Net-(IC5A-OUT)") (class "Default")
      (node (ref "IC5") (pin "1") (pinfunction "OUT_1") (pintype "output"))
      (node (ref "R22") (pin "2") (pinfunction "2_2") (pintype "passive"))
      (node (ref "R23") (pin "1") (pinfunction "1_1") (pintype "passive"))
    )
    (net (code "30") (name "Net-(IC5B-+IN)") (class "Default")
      (node (ref "C22") (pin "1") (pinfunction "1_1") (pintype "passive"))
      (node (ref "IC5") (pin "5") (pinfunction "+IN_5") (pintype "input"))
      (node (ref "R15") (pin "1") (pinfunction "1_1") (pintype "passive"))
    )
    (net (code "31") (name "Net-(IC5B--IN)") (class "Default")
      (node (ref "C19") (pin "2") (pinfunction "2_2") (pintype "passive"))
      (node (ref "IC5") (pin "6") (pinfunction "-IN_6") (pintype "input"))
      (node (ref "IC5") (pin "7") (pinfunction "OUT_7") (pintype "output"))
      (node (ref "R20") (pin "2") (pinfunction "2_2") (pintype "passive"))
    )
    (net (code "32") (name "Net-(IC6A-+IN)") (class "Default")
      (node (ref "C21") (pin "2") (pinfunction "2_2") (pintype "passive"))
      (node (ref "IC6") (pin "3") (pinfunction "+IN_3") (pintype "input"))
      (node (ref "IC6") (pin "6") (pinfunction "-IN_6") (pintype "input"))
      (node (ref "IC6") (pin "7") (pinfunction "OUT_7") (pintype "output"))
    )
    (net (code "33") (name "Net-(IC6A--IN)") (class "Default")
      (node (ref "IC6") (pin "2") (pinfunction "-IN_2") (pintype "input"))
      (node (ref "R25") (pin "2") (pinfunction "2_2") (pintype "passive"))
      (node (ref "R26") (pin "2") (pinfunction "2_2") (pintype "passive"))
    )
    (net (code "34") (name "Net-(IC6A-OUT)") (class "Default")
      (node (ref "IC6") (pin "1") (pinfunction "OUT_1") (pintype "output"))
      (node (ref "R24") (pin "2") (pinfunction "2_2") (pintype "passive"))
      (node (ref "R25") (pin "1") (pinfunction "1_1") (pintype "passive"))
    )
    (net (code "35") (name "Net-(IC6B-+IN)") (class "Default")
      (node (ref "C23") (pin "1") (pinfunction "1_1") (pintype "passive"))
      (node (ref "IC6") (pin "5") (pinfunction "+IN_5") (pintype "input"))
      (node (ref "R16") (pin "1") (pinfunction "1_1") (pintype "passive"))
    )
    (net (code "36") (name "Net-(IC8A--IN)") (class "Default")
      (node (ref "C31") (pin "1") (pinfunction "1_1") (pintype "passive"))
      (node (ref "IC8") (pin "2") (pinfunction "-IN_2") (pintype "input"))
      (node (ref "R37") (pin "2") (pinfunction "2_2") (pintype "passive"))
      (node (ref "R38") (pin "1") (pinfunction "1_1") (pintype "passive"))
      (node (ref "R39") (pin "1") (pinfunction "1_1") (pintype "passive"))
    )
    (net (code "37") (name "Net-(IC8B--IN)") (class "Default")
      (node (ref "C27") (pin "1") (pinfunction "1_1") (pintype "passive"))
      (node (ref "IC8") (pin "6") (pinfunction "-IN_6") (pintype "input"))
      (node (ref "R34") (pin "2") (pinfunction "2_2") (pintype "passive"))
      (node (ref "R35") (pin "1") (pinfunction "1_1") (pintype "passive"))
      (node (ref "R36") (pin "1") (pinfunction "1_1") (pintype "passive"))
    )
    (net (code "38") (name "Net-(IC9A--IN)") (class "Default")
      (node (ref "C32") (pin "1") (pinfunction "1_1") (pintype "passive"))
      (node (ref "IC9") (pin "2") (pinfunction "-IN_2") (pintype "input"))
      (node (ref "R40") (pin "2") (pinfunction "2_2") (pintype "passive"))
      (node (ref "R41") (pin "1") (pinfunction "1_1") (pintype "passive"))
      (node (ref "R42") (pin "1") (pinfunction "1_1") (pintype "passive"))
    )
    (net (code "39") (name "Net-(IC9B--IN)") (class "Default")
      (node (ref "C34") (pin "1") (pinfunction "1_1") (pintype "passive"))
      (node (ref "IC9") (pin "6") (pinfunction "-IN_6") (pintype "input"))
      (node (ref "R43") (pin "1") (pinfunction "1_1") (pintype "passive"))
      (node (ref "R44") (pin "1") (pinfunction "1_1") (pintype "passive"))
      (node (ref "R45") (pin "2") (pinfunction "2_2") (pintype "passive"))
    )
    (net (code "40") (name "Net-(IC9C--IN)") (class "Default")
      (node (ref "C28") (pin "1") (pinfunction "1_1") (pintype "passive"))
      (node (ref "IC9") (pin "9") (pinfunction "-IN_9") (pintype "input"))
      (node (ref "R31") (pin "1") (pinfunction "1_1") (pintype "passive"))
      (node (ref "R32") (pin "1") (pinfunction "1_1") (pintype "passive"))
      (node (ref "R33") (pin "2") (pinfunction "2_2") (pintype "passive"))
    )
    (net (code "41") (name "Net-(IC9D--IN)") (class "Default")
      (node (ref "C29") (pin "1") (pinfunction "1_1") (pintype "passive"))
      (node (ref "IC9") (pin "13") (pinfunction "-IN_13") (pintype "input"))
      (node (ref "R28") (pin "2") (pinfunction "2_2") (pintype "passive"))
      (node (ref "R29") (pin "1") (pinfunction "1_1") (pintype "passive"))
      (node (ref "R30") (pin "1") (pinfunction "1_1") (pintype "passive"))
    )
    (net (code "42") (name "Net-(J1-3)") (class "Default")
      (node (ref "J1") (pin "P3") (pinfunction "3_P3") (pintype "passive"))
      (node (ref "R42") (pin "2") (pinfunction "2_2") (pintype "passive"))
    )
    (net (code "43") (name "Net-(J2-3)") (class "Default")
      (node (ref "J2") (pin "P3") (pinfunction "3_P3") (pintype "passive"))
      (node (ref "R29") (pin "2") (pinfunction "2_2") (pintype "passive"))
    )
    (net (code "44") (name "Net-(J3-3)") (class "Default")
      (node (ref "J3") (pin "P3") (pinfunction "3_P3") (pintype "passive"))
      (node (ref "R32") (pin "2") (pinfunction "2_2") (pintype "passive"))
    )
    (net (code "45") (name "Net-(J4-3)") (class "Default")
      (node (ref "J4") (pin "P3") (pinfunction "3_P3") (pintype "passive"))
      (node (ref "R55") (pin "1") (pinfunction "1_1") (pintype "passive"))
    )
    (net (code "46") (name "Net-(J5-3)") (class "Default")
      (node (ref "J5") (pin "P3") (pinfunction "3_P3") (pintype "passive"))
      (node (ref "R56") (pin "1") (pinfunction "1_1") (pintype "passive"))
    )
    (net (code "47") (name "Net-(J6-3)") (class "Default")
      (node (ref "J6") (pin "P3") (pinfunction "3_P3") (pintype "passive"))
      (node (ref "R39") (pin "2") (pinfunction "2_2") (pintype "passive"))
    )
    (net (code "48") (name "Net-(J7-2)") (class "Default")
      (node (ref "J7") (pin "P2") (pinfunction "2_P2") (pintype "passive"))
      (node (ref "R46") (pin "1") (pinfunction "1_1") (pintype "passive"))
    )
    (net (code "49") (name "Net-(J7-3)") (class "Default")
      (node (ref "J7") (pin "P3") (pinfunction "3_P3") (pintype "passive"))
      (node (ref "R36") (pin "2") (pinfunction "2_2") (pintype "passive"))
    )
    (net (code "50") (name "Net-(J8-2)") (class "Default")
      (node (ref "J8") (pin "P2") (pinfunction "2_P2") (pintype "passive"))
      (node (ref "R60") (pin "2") (pinfunction "2_2") (pintype "passive"))
    )
    (net (code "51") (name "Net-(J8-3)") (class "Default")
      (node (ref "J8") (pin "P3") (pinfunction "3_P3") (pintype "passive"))
      (node (ref "R44") (pin "2") (pinfunction "2_2") (pintype "passive"))
    )
    (net (code "52") (name "Net-(J9-3)") (class "Default")
      (node (ref "J9") (pin "P3") (pinfunction "3_P3") (pintype "passive"))
      (node (ref "R54") (pin "1") (pinfunction "1_1") (pintype "passive"))
    )
    (net (code "53") (name "Net-(J10-3)") (class "Default")
      (node (ref "J10") (pin "P3") (pinfunction "3_P3") (pintype "passive"))
      (node (ref "Q5") (pin "C") (pinfunction "C_C") (pintype "passive"))
      (node (ref "R50") (pin "2") (pinfunction "2_2") (pintype "passive"))
      (node (ref "R51") (pin "1") (pinfunction "1_1") (pintype "passive"))
    )
    (net (code "54") (name "Net-(J11-3)") (class "Default")
      (node (ref "J11") (pin "P3") (pinfunction "3_P3") (pintype "passive"))
      (node (ref "Q6") (pin "C") (pinfunction "C_C") (pintype "passive"))
      (node (ref "R52") (pin "2") (pinfunction "2_2") (pintype "passive"))
      (node (ref "R53") (pin "1") (pinfunction "1_1") (pintype "passive"))
    )
    (net (code "55") (name "Net-(J12-3)") (class "Default")
      (node (ref "J12") (pin "P3") (pinfunction "3_P3") (pintype "passive"))
      (node (ref "R24") (pin "1") (pinfunction "1_1") (pintype "passive"))
    )
    (net (code "56") (name "Net-(J13-3)") (class "Default")
      (node (ref "J13") (pin "P3") (pinfunction "3_P3") (pintype "passive"))
      (node (ref "R22") (pin "1") (pinfunction "1_1") (pintype "passive"))
    )
    (net (code "57") (name "Net-(LED1-GRN)") (class "Default")
      (node (ref "LED1") (pin "1") (pinfunction "GRN_1") (pintype "bidirectional"))
      (node (ref "R2") (pin "2") (pinfunction "2_2") (pintype "passive"))
    )
    (net (code "58") (name "Net-(LED1-RED)") (class "Default")
      (node (ref "LED1") (pin "3") (pinfunction "RED_3") (pintype "bidirectional"))
      (node (ref "R3") (pin "2") (pinfunction "2_2") (pintype "passive"))
    )
    (net (code "59") (name "Net-(LED2-GRN)") (class "Default")
      (node (ref "LED2") (pin "1") (pinfunction "GRN_1") (pintype "bidirectional"))
      (node (ref "R4") (pin "2") (pinfunction "2_2") (pintype "passive"))
    )
    (net (code "60") (name "Net-(LED2-RED)") (class "Default")
      (node (ref "LED2") (pin "3") (pinfunction "RED_3") (pintype "bidirectional"))
      (node (ref "R7") (pin "2") (pinfunction "2_2") (pintype "passive"))
    )
    (net (code "61") (name "Net-(LED3-GRN)") (class "Default")
      (node (ref "LED3") (pin "1") (pinfunction "GRN_1") (pintype "bidirectional"))
      (node (ref "R9") (pin "2") (pinfunction "2_2") (pintype "passive"))
    )
    (net (code "62") (name "Net-(LED3-RED)") (class "Default")
      (node (ref "LED3") (pin "3") (pinfunction "RED_3") (pintype "bidirectional"))
      (node (ref "R10") (pin "2") (pinfunction "2_2") (pintype "passive"))
    )
    (net (code "63") (name "Net-(Q2-PadB)") (class "Default")
      (node (ref "Q2") (pin "B") (pinfunction "B_B") (pintype "passive"))
      (node (ref "R55") (pin "2") (pinfunction "2_2") (pintype "passive"))
    )
    (net (code "64") (name "Net-(Q3-PadB)") (class "Default")
      (node (ref "Q3") (pin "B") (pinfunction "B_B") (pintype "passive"))
      (node (ref "R54") (pin "2") (pinfunction "2_2") (pintype "passive"))
    )
    (net (code "65") (name "Net-(Q4-PadB)") (class "Default")
      (node (ref "Q4") (pin "B") (pinfunction "B_B") (pintype "passive"))
      (node (ref "R56") (pin "2") (pinfunction "2_2") (pintype "passive"))
    )
    (net (code "66") (name "Net-(Q5-PadB)") (class "Default")
      (node (ref "Q5") (pin "B") (pinfunction "B_B") (pintype "passive"))
      (node (ref "R57") (pin "2") (pinfunction "2_2") (pintype "passive"))
    )
    (net (code "67") (name "Net-(Q6-PadB)") (class "Default")
      (node (ref "Q6") (pin "B") (pinfunction "B_B") (pintype "passive"))
      (node (ref "R58") (pin "2") (pinfunction "2_2") (pintype "passive"))
    )
    (net (code "68") (name "Net-(R5-E)") (class "Default")
      (node (ref "R5") (pin "P$1") (pinfunction "E_P$1") (pintype "passive"))
      (node (ref "R8") (pin "2") (pinfunction "2_2") (pintype "passive"))
    )
    (net (code "69") (name "Net-(R5-S)") (class "Default")
      (node (ref "R38") (pin "2") (pinfunction "2_2") (pintype "passive"))
      (node (ref "R5") (pin "P$2") (pinfunction "S_P$2") (pintype "passive"))
    )
    (net (code "70") (name "Net-(R17-S)") (class "Default")
      (node (ref "R17") (pin "P$2") (pinfunction "S_P$2") (pintype "passive"))
      (node (ref "R41") (pin "2") (pinfunction "2_2") (pintype "passive"))
    )
    (net (code "71") (name "Net-(R18-S)") (class "Default")
      (node (ref "R18") (pin "P$2") (pinfunction "S_P$2") (pintype "passive"))
      (node (ref "R30") (pin "2") (pinfunction "2_2") (pintype "passive"))
    )
    (net (code "72") (name "Net-(R19-S)") (class "Default")
      (node (ref "R19") (pin "P$2") (pinfunction "S_P$2") (pintype "passive"))
      (node (ref "R31") (pin "2") (pinfunction "2_2") (pintype "passive"))
    )
    (net (code "73") (name "Net-(R59-A)") (class "Default")
      (node (ref "R21") (pin "2") (pinfunction "2_2") (pintype "passive"))
      (node (ref "R59") (pin "1") (pinfunction "A_1") (pintype "passive"))
    )
    (net (code "74") (name "Net-(UC1-PB4{slash}NJTRST)") (class "Default")
      (node (ref "R2") (pin "1") (pinfunction "1_1") (pintype "passive"))
      (node (ref "UC1") (pin "40") (pinfunction "PB4/NJTRST_40") (pintype "bidirectional"))
    )
    (net (code "75") (name "Net-(UC1-PB5{slash}I2C1_SMBA)") (class "Default")
      (node (ref "R3") (pin "1") (pinfunction "1_1") (pintype "passive"))
      (node (ref "UC1") (pin "41") (pinfunction "PB5/I2C1_SMBA_41") (pintype "input"))
    )
    (net (code "76") (name "Net-(UC1-PB6{slash}I2C1_SCL{slash}TIM4_CH1)") (class "Default")
      (node (ref "R4") (pin "1") (pinfunction "1_1") (pintype "passive"))
      (node (ref "UC1") (pin "42") (pinfunction "PB6/I2C1_SCL/TIM4_CH1_42") (pintype "input"))
    )
    (net (code "77") (name "Net-(UC1-PB7{slash}I2C1_SDA{slash}TIM4_CH2)") (class "Default")
      (node (ref "R7") (pin "1") (pinfunction "1_1") (pintype "passive"))
      (node (ref "UC1") (pin "43") (pinfunction "PB7/I2C1_SDA/TIM4_CH2_43") (pintype "bidirectional"))
    )
    (net (code "78") (name "Net-(UC1-PB8{slash}TIM4_CH3)") (class "Default")
      (node (ref "R9") (pin "1") (pinfunction "1_1") (pintype "passive"))
      (node (ref "UC1") (pin "45") (pinfunction "PB8/TIM4_CH3_45") (pintype "bidirectional"))
    )
    (net (code "79") (name "Net-(UC1-PB9{slash}TIM4_CH4)") (class "Default")
      (node (ref "R10") (pin "1") (pinfunction "1_1") (pintype "passive"))
      (node (ref "UC1") (pin "46") (pinfunction "PB9/TIM4_CH4_46") (pintype "input"))
    )
    (net (code "80") (name "Net-(UC1-PD0-OSC_IN)") (class "Default")
      (node (ref "C2") (pin "2") (pinfunction "2_2") (pintype "passive"))
      (node (ref "Q1") (pin "2") (pinfunction "2_2") (pintype "passive"))
      (node (ref "UC1") (pin "5") (pinfunction "PD0-OSC_IN_5") (pintype "input"))
    )
    (net (code "81") (name "Net-(UC1-PD1-OSC_OUT)") (class "Default")
      (node (ref "C17") (pin "2") (pinfunction "2_2") (pintype "passive"))
      (node (ref "Q1") (pin "1") (pinfunction "1_1") (pintype "passive"))
      (node (ref "UC1") (pin "6") (pinfunction "PD1-OSC_OUT_6") (pintype "input"))
    )
    (net (code "82") (name "PROC_ADC") (class "Default")
      (node (ref "C28") (pin "2") (pinfunction "2_2") (pintype "passive"))
      (node (ref "IC9") (pin "8") (pinfunction "OUT_8") (pintype "output"))
      (node (ref "R33") (pin "1") (pinfunction "1_1") (pintype "passive"))
      (node (ref "UC1") (pin "17") (pinfunction "PA7/SPI1_MOSI/ADC12_IN7/TIM3_CH2_17") (pintype "bidirectional"))
    )
    (net (code "83") (name "RANGE_SW") (class "Default")
      (node (ref "SW4") (pin "3") (pinfunction "S_3") (pintype "passive"))
      (node (ref "SW4") (pin "4") (pinfunction "S1_4") (pintype "passive"))
      (node (ref "UC1") (pin "11") (pinfunction "PA1/USART2_RTS/ADC12_IN1/TIM2_CH2_11") (pintype "bidirectional"))
    )
    (net (code "84") (name "RESET") (class "Default")
      (node (ref "JTAG") (pin "10") (pinfunction "10_10") (pintype "passive"))
      (node (ref "UC1") (pin "7") (pinfunction "NRST_7") (pintype "input"))
    )
    (net (code "85") (name "RX") (class "Default")
      (node (ref "UC1") (pin "31") (pinfunction "PA10/USART1_RX/TIM1_CH3_31") (pintype "bidirectional"))
    )
    (net (code "86") (name "SHAPE_ADC") (class "Default")
      (node (ref "C32") (pin "2") (pinfunction "2_2") (pintype "passive"))
      (node (ref "IC9") (pin "1") (pinfunction "OUT_1") (pintype "output"))
      (node (ref "R40") (pin "1") (pinfunction "1_1") (pintype "passive"))
      (node (ref "UC1") (pin "15") (pinfunction "PA5/SPI1_SCK/ADC12_IN5_15") (pintype "bidirectional"))
    )
    (net (code "87") (name "START") (class "Default")
      (node (ref "Q2") (pin "C") (pinfunction "C_C") (pintype "passive"))
      (node (ref "R47") (pin "1") (pinfunction "1_1") (pintype "passive"))
      (node (ref "UC1") (pin "22") (pinfunction "PB11/I2C2_SDA/USART3_RX_22") (pintype "input"))
    )
    (net (code "88") (name "TX") (class "Default")
      (node (ref "UC1") (pin "30") (pinfunction "PA9/USART1_TX/TIM1_CH2_30") (pintype "input"))
    )
    (net (code "89") (name "UNI") (class "Default")
      (node (ref "IC4") (pin "4") (pinfunction "OUTA_4") (pintype "output"))
      (node (ref "R14") (pin "2") (pinfunction "2_2") (pintype "passive"))
    )
    (net (code "90") (name "VCC") (class "Default")
      (node (ref "C18") (pin "1") (pinfunction "1_1") (pintype "passive"))
      (node (ref "C20") (pin "1") (pinfunction "1_1") (pintype "passive"))
      (node (ref "C3") (pin "+") (pinfunction "+_+") (pintype "passive"))
      (node (ref "C8") (pin "+") (pinfunction "+_+") (pintype "passive"))
      (node (ref "D1") (pin "C") (pinfunction "C_C") (pintype "passive"))
      (node (ref "IC1") (pin "3") (pinfunction "VIN_3") (pintype "input"))
      (node (ref "IC3") (pin "3") (pinfunction "VIN_3") (pintype "input"))
      (node (ref "IC5") (pin "8") (pinfunction "V+_8") (pintype "power_in"))
      (node (ref "IC6") (pin "8") (pinfunction "V+_8") (pintype "power_in"))
      (node (ref "R51") (pin "2") (pinfunction "2_2") (pintype "passive"))
      (node (ref "R53") (pin "2") (pinfunction "2_2") (pintype "passive"))
      (node (ref "R60") (pin "1") (pinfunction "1_1") (pintype "passive"))
    )
    (net (code "91") (name "VEE") (class "Default")
      (node (ref "C10") (pin "-") (pinfunction "-_-") (pintype "passive"))
      (node (ref "C24") (pin "2") (pinfunction "2_2") (pintype "passive"))
      (node (ref "C25") (pin "2") (pinfunction "2_2") (pintype "passive"))
      (node (ref "D2") (pin "A") (pinfunction "A_A") (pintype "passive"))
      (node (ref "IC5") (pin "4") (pinfunction "V-_4") (pintype "power_in"))
      (node (ref "IC6") (pin "4") (pinfunction "V-_4") (pintype "power_in"))
      (node (ref "R27") (pin "1") (pinfunction "1_1") (pintype "passive"))
    )
    (net (code "92") (name "VOCT_ADC") (class "Default")
      (node (ref "C31") (pin "2") (pinfunction "2_2") (pintype "passive"))
      (node (ref "IC8") (pin "1") (pinfunction "OUT_1") (pintype "output"))
      (node (ref "R37") (pin "1") (pinfunction "1_1") (pintype "passive"))
      (node (ref "UC1") (pin "13") (pinfunction "PA3/USART2_RX/ADC12_IN3/TIM2_CH4_13") (pintype "bidirectional"))
    )
    (net (code "93") (name "unconnected-(J1-2-PadP2)") (class "Default")
      (node (ref "J1") (pin "P2") (pinfunction "2_P2") (pintype "passive"))
    )
    (net (code "94") (name "unconnected-(J2-2-PadP2)") (class "Default")
      (node (ref "J2") (pin "P2") (pinfunction "2_P2") (pintype "passive"))
    )
    (net (code "95") (name "unconnected-(J3-2-PadP2)") (class "Default")
      (node (ref "J3") (pin "P2") (pinfunction "2_P2") (pintype "passive"))
    )
    (net (code "96") (name "unconnected-(J6-2-PadP2)") (class "Default")
      (node (ref "J6") (pin "P2") (pinfunction "2_P2") (pintype "passive"))
    )
    (net (code "97") (name "unconnected-(J10-2-PadP2)") (class "Default")
      (node (ref "J10") (pin "P2") (pinfunction "2_P2") (pintype "passive"))
    )
    (net (code "98") (name "unconnected-(J11-2-PadP2)") (class "Default")
      (node (ref "J11") (pin "P2") (pinfunction "2_P2") (pintype "passive"))
    )
    (net (code "99") (name "unconnected-(J12-2-PadP2)") (class "Default")
      (node (ref "J12") (pin "P2") (pinfunction "2_P2") (pintype "passive"))
    )
    (net (code "100") (name "unconnected-(J13-2-PadP2)") (class "Default")
      (node (ref "J13") (pin "P2") (pinfunction "2_P2") (pintype "passive"))
    )
    (net (code "101") (name "unconnected-(JTAG-Pad7)") (class "Default")
      (node (ref "JTAG") (pin "7") (pinfunction "7_7") (pintype "passive"))
    )
    (net (code "102") (name "unconnected-(UC1-PA8{slash}USART1_CK{slash}TIM1_CH1{slash}MCO-Pad29)") (class "Default")
      (node (ref "UC1") (pin "29") (pinfunction "PA8/USART1_CK/TIM1_CH1/MCO_29") (pintype "bidirectional"))
    )
    (net (code "103") (name "unconnected-(UC1-PB14{slash}SPI2_MISO{slash}USART3_RTS{slash}TIM1_CH2N-Pad27)") (class "Default")
      (node (ref "UC1") (pin "27") (pinfunction "PB14/SPI2_MISO/USART3_RTS/TIM1_CH2N_27") (pintype "input"))
    )
    (net (code "104") (name "unconnected-(UC1-PC13-TAMPER-RTC-Pad2)") (class "Default")
      (node (ref "UC1") (pin "2") (pinfunction "PC13-TAMPER-RTC_2") (pintype "input"))
    )
    (net (code "105") (name "unconnected-(UC1-PC14-OSC32_IN-Pad3)") (class "Default")
      (node (ref "UC1") (pin "3") (pinfunction "PC14-OSC32_IN_3") (pintype "input"))
    )
    (net (code "106") (name "unconnected-(UC1-PC15-OSC32_OUT-Pad4)") (class "Default")
      (node (ref "UC1") (pin "4") (pinfunction "PC15-OSC32_OUT_4") (pintype "input"))
    )
  )
)
